# xtree.net
KiCad netlist of a schematic drawn in EAGLE
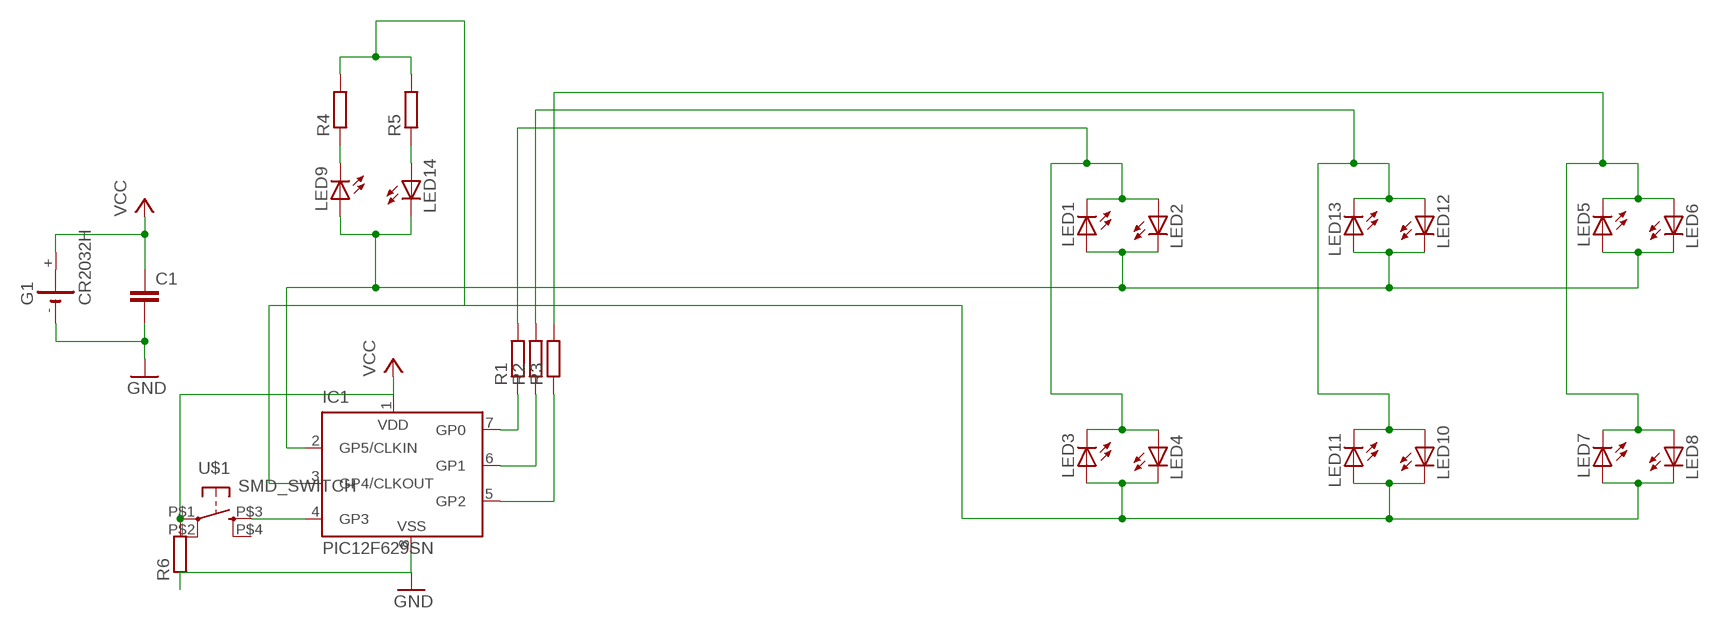
[diagram p0: schematic, sheet 1]

(export (version "E")
  (design (tool "Eeschema 10.0.6"))
  (components
    (comp (ref "C1")
      (value "C-EUC1206K")
      (footprint "eagle-import:C1206K")
      (libsource (lib "eagle-import") (part "C-EUC1206K"))
    )
    (comp (ref "G1")
      (value "CR2032H")
      (footprint "eagle-import:CR2032H")
      (libsource (lib "eagle-import") (part "CR2032H"))
    )
    (comp (ref "IC1")
      (value "PIC12F629SN")
      (footprint "eagle-import:SO-08")
      (fields (field (name "MF") "MICROCHIP") (field (name "MPN") "PIC12F629-I/SN"))
      (libsource (lib "eagle-import") (part "PIC12F6SN29"))
    )
    (comp (ref "LED1")
      (value "LED_E")
      (footprint "eagle-import:LED_1206")
      (libsource (lib "eagle-import") (part "LED_E"))
    )
    (comp (ref "LED2")
      (value "LED_E")
      (footprint "eagle-import:LED_1206")
      (libsource (lib "eagle-import") (part "LED_E"))
    )
    (comp (ref "LED3")
      (value "LED_E")
      (footprint "eagle-import:LED_1206")
      (libsource (lib "eagle-import") (part "LED_E"))
    )
    (comp (ref "LED4")
      (value "LED_E")
      (footprint "eagle-import:LED_1206")
      (libsource (lib "eagle-import") (part "LED_E"))
    )
    (comp (ref "LED5")
      (value "LED_E")
      (footprint "eagle-import:LED_1206")
      (libsource (lib "eagle-import") (part "LED_E"))
    )
    (comp (ref "LED6")
      (value "LED_E")
      (footprint "eagle-import:LED_1206")
      (libsource (lib "eagle-import") (part "LED_E"))
    )
    (comp (ref "LED7")
      (value "LED_E")
      (footprint "eagle-import:LED_1206")
      (libsource (lib "eagle-import") (part "LED_E"))
    )
    (comp (ref "LED8")
      (value "LED_E")
      (footprint "eagle-import:LED_1206")
      (libsource (lib "eagle-import") (part "LED_E"))
    )
    (comp (ref "LED9")
      (value "LED_E")
      (footprint "eagle-import:LED_1206")
      (libsource (lib "eagle-import") (part "LED_E"))
    )
    (comp (ref "LED10")
      (value "LED_E")
      (footprint "eagle-import:LED_1206")
      (libsource (lib "eagle-import") (part "LED_E"))
    )
    (comp (ref "LED11")
      (value "LED_E")
      (footprint "eagle-import:LED_1206")
      (libsource (lib "eagle-import") (part "LED_E"))
    )
    (comp (ref "LED12")
      (value "LED_E")
      (footprint "eagle-import:LED_1206")
      (libsource (lib "eagle-import") (part "LED_E"))
    )
    (comp (ref "LED13")
      (value "LED_E")
      (footprint "eagle-import:LED_1206")
      (libsource (lib "eagle-import") (part "LED_E"))
    )
    (comp (ref "LED14")
      (value "LED_E")
      (footprint "eagle-import:LED_1206")
      (libsource (lib "eagle-import") (part "LED_E"))
    )
    (comp (ref "R1")
      (value "R-EU_R0603")
      (footprint "eagle-import:R0603")
      (libsource (lib "eagle-import") (part "R-EU_R0603"))
    )
    (comp (ref "R2")
      (value "R-EU_R0603")
      (footprint "eagle-import:R0603")
      (libsource (lib "eagle-import") (part "R-EU_R0603"))
    )
    (comp (ref "R3")
      (value "R-EU_R0603")
      (footprint "eagle-import:R0603")
      (libsource (lib "eagle-import") (part "R-EU_R0603"))
    )
    (comp (ref "R4")
      (value "R-EU_R0603")
      (footprint "eagle-import:R0603")
      (libsource (lib "eagle-import") (part "R-EU_R0603"))
    )
    (comp (ref "R5")
      (value "R-EU_R0603")
      (footprint "eagle-import:R0603")
      (libsource (lib "eagle-import") (part "R-EU_R0603"))
    )
    (comp (ref "R6")
      (value "R-EU_R0603")
      (footprint "eagle-import:R0603")
      (libsource (lib "eagle-import") (part "R-EU_R0603"))
    )
    (comp (ref "U$1")
      (value "SMD_SWITCH")
      (footprint "eagle-import:SMD_BUTTON")
      (libsource (lib "eagle-import") (part "SMD_SWITCH"))
    )
  )
  (nets
    (net (code "1") (name "GND") (class "Default")
      (node (ref "C1") (pin "2") (pinfunction "2_2") (pintype "passive"))
      (node (ref "G1") (pin "-") (pinfunction "-_-") (pintype "passive"))
      (node (ref "IC1") (pin "8") (pinfunction "VSS_8") (pintype "power_in"))
      (node (ref "R6") (pin "1") (pinfunction "1_1") (pintype "passive"))
    )
    (net (code "2") (name "Net-(IC1-GP0)") (class "Default")
      (node (ref "IC1") (pin "7") (pinfunction "GP0_7") (pintype "bidirectional"))
      (node (ref "R1") (pin "1") (pinfunction "1_1") (pintype "passive"))
    )
    (net (code "3") (name "Net-(IC1-GP1)") (class "Default")
      (node (ref "IC1") (pin "6") (pinfunction "GP1_6") (pintype "bidirectional"))
      (node (ref "R2") (pin "1") (pinfunction "1_1") (pintype "passive"))
    )
    (net (code "4") (name "Net-(IC1-GP2)") (class "Default")
      (node (ref "IC1") (pin "5") (pinfunction "GP2_5") (pintype "bidirectional"))
      (node (ref "R3") (pin "1") (pinfunction "1_1") (pintype "passive"))
    )
    (net (code "5") (name "Net-(IC1-GP3)") (class "Default")
      (node (ref "IC1") (pin "4") (pinfunction "GP3_4") (pintype "input"))
      (node (ref "U$1") (pin "P$3") (pinfunction "S_P$3") (pintype "passive"))
    )
    (net (code "6") (name "Net-(IC1-GP4{slash}CLKOUT)") (class "Default")
      (node (ref "IC1") (pin "3") (pinfunction "GP4/CLKOUT_3") (pintype "bidirectional"))
      (node (ref "LED10") (pin "C") (pinfunction "C_C") (pintype "passive"))
      (node (ref "LED11") (pin "A") (pinfunction "A_A") (pintype "passive"))
      (node (ref "LED3") (pin "A") (pinfunction "A_A") (pintype "passive"))
      (node (ref "LED4") (pin "C") (pinfunction "C_C") (pintype "passive"))
      (node (ref "LED7") (pin "A") (pinfunction "A_A") (pintype "passive"))
      (node (ref "LED8") (pin "C") (pinfunction "C_C") (pintype "passive"))
      (node (ref "R4") (pin "2") (pinfunction "2_2") (pintype "passive"))
      (node (ref "R5") (pin "2") (pinfunction "2_2") (pintype "passive"))
    )
    (net (code "7") (name "Net-(IC1-GP5{slash}CLKIN)") (class "Default")
      (node (ref "IC1") (pin "2") (pinfunction "GP5/CLKIN_2") (pintype "bidirectional"))
      (node (ref "LED1") (pin "A") (pinfunction "A_A") (pintype "passive"))
      (node (ref "LED12") (pin "C") (pinfunction "C_C") (pintype "passive"))
      (node (ref "LED13") (pin "A") (pinfunction "A_A") (pintype "passive"))
      (node (ref "LED14") (pin "C") (pinfunction "C_C") (pintype "passive"))
      (node (ref "LED2") (pin "C") (pinfunction "C_C") (pintype "passive"))
      (node (ref "LED5") (pin "A") (pinfunction "A_A") (pintype "passive"))
      (node (ref "LED6") (pin "C") (pinfunction "C_C") (pintype "passive"))
      (node (ref "LED9") (pin "A") (pinfunction "A_A") (pintype "passive"))
    )
    (net (code "8") (name "Net-(LED1-PadC)") (class "Default")
      (node (ref "LED1") (pin "C") (pinfunction "C_C") (pintype "passive"))
      (node (ref "LED2") (pin "A") (pinfunction "A_A") (pintype "passive"))
      (node (ref "LED3") (pin "C") (pinfunction "C_C") (pintype "passive"))
      (node (ref "LED4") (pin "A") (pinfunction "A_A") (pintype "passive"))
      (node (ref "R1") (pin "2") (pinfunction "2_2") (pintype "passive"))
    )
    (net (code "9") (name "Net-(LED5-PadC)") (class "Default")
      (node (ref "LED5") (pin "C") (pinfunction "C_C") (pintype "passive"))
      (node (ref "LED6") (pin "A") (pinfunction "A_A") (pintype "passive"))
      (node (ref "LED7") (pin "C") (pinfunction "C_C") (pintype "passive"))
      (node (ref "LED8") (pin "A") (pinfunction "A_A") (pintype "passive"))
      (node (ref "R3") (pin "2") (pinfunction "2_2") (pintype "passive"))
    )
    (net (code "10") (name "Net-(LED9-PadC)") (class "Default")
      (node (ref "LED9") (pin "C") (pinfunction "C_C") (pintype "passive"))
      (node (ref "R4") (pin "1") (pinfunction "1_1") (pintype "passive"))
    )
    (net (code "11") (name "Net-(LED10-PadA)") (class "Default")
      (node (ref "LED10") (pin "A") (pinfunction "A_A") (pintype "passive"))
      (node (ref "LED11") (pin "C") (pinfunction "C_C") (pintype "passive"))
      (node (ref "LED12") (pin "A") (pinfunction "A_A") (pintype "passive"))
      (node (ref "LED13") (pin "C") (pinfunction "C_C") (pintype "passive"))
      (node (ref "R2") (pin "2") (pinfunction "2_2") (pintype "passive"))
    )
    (net (code "12") (name "Net-(LED14-PadA)") (class "Default")
      (node (ref "LED14") (pin "A") (pinfunction "A_A") (pintype "passive"))
      (node (ref "R5") (pin "1") (pinfunction "1_1") (pintype "passive"))
    )
    (net (code "13") (name "VCC") (class "Default")
      (node (ref "C1") (pin "1") (pinfunction "1_1") (pintype "passive"))
      (node (ref "G1") (pin "+") (pinfunction "+_+") (pintype "passive"))
      (node (ref "IC1") (pin "1") (pinfunction "VDD_1") (pintype "power_in"))
      (node (ref "R6") (pin "2") (pinfunction "2_2") (pintype "passive"))
      (node (ref "U$1") (pin "P$1") (pinfunction "P_P$1") (pintype "passive"))
    )
    (net (code "14") (name "unconnected-(G1-+-Pad+@1)") (class "Default")
      (node (ref "G1") (pin "+@1") (pinfunction "+_+@1") (pintype "passive"))
    )
    (net (code "15") (name "unconnected-(U$1-P1-PadP$2)") (class "Default")
      (node (ref "U$1") (pin "P$2") (pinfunction "P1_P$2") (pintype "passive"))
    )
    (net (code "16") (name "unconnected-(U$1-S1-PadP$4)") (class "Default")
      (node (ref "U$1") (pin "P$4") (pinfunction "S1_P$4") (pintype "passive"))
    )
  )
)
